# TCA6408A.net
KiCad netlist of a schematic drawn in EasyEDA Pro
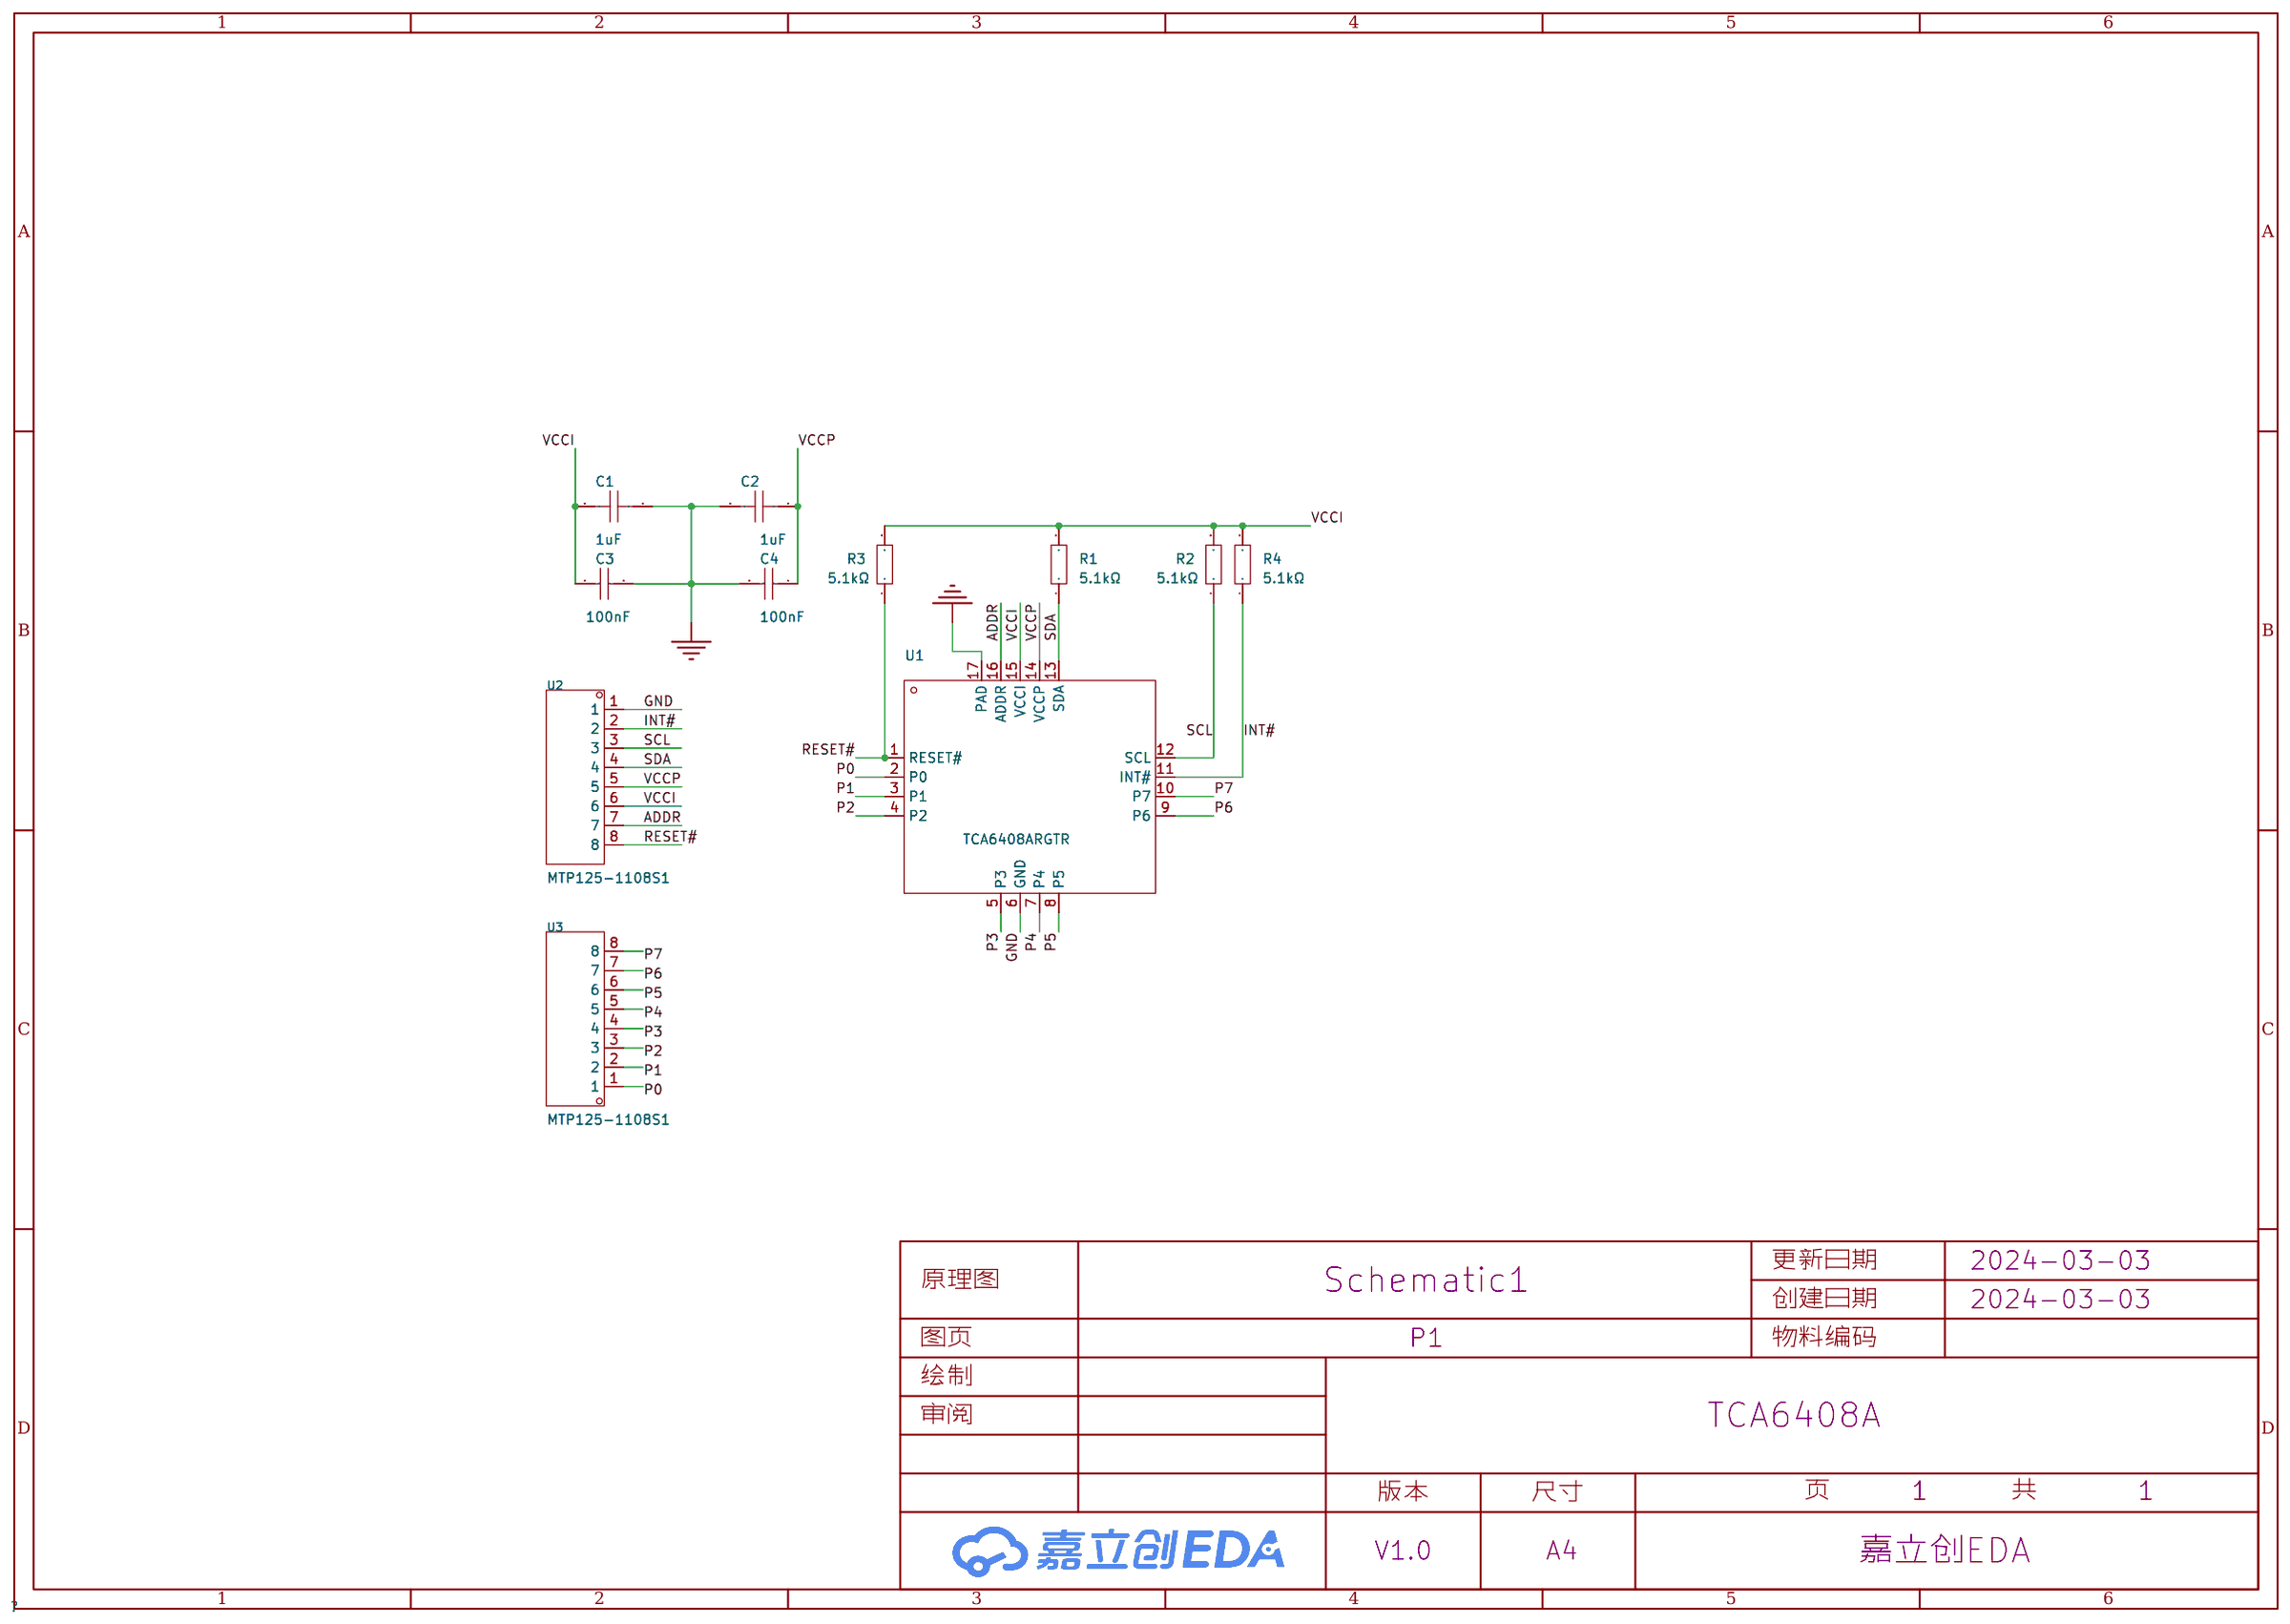
[diagram p0: schematic sheet]

(export (version "E")
  (design (tool "Eeschema 10.0.6"))
  (components
    (comp (ref "C1")
      (value "1uF")
      (footprint "easyedapro:C0402")
      (description "容值:1uF;精度:±10%;额定电压:25V;材质(温度系数):X5R;")
      (fields
        (field (name "Manufacturer Part") "CL05A105KA5NQNC")
        (field (name "Manufacturer") "SAMSUNG(三星)")
      )
      (libsource (lib "easyedapro") (part "CL05A105KA5NQNC"))
    )
    (comp (ref "C2")
      (value "1uF")
      (footprint "easyedapro:C0402")
      (description "容值:1uF;精度:±10%;额定电压:25V;材质(温度系数):X5R;")
      (fields
        (field (name "Manufacturer Part") "CL05A105KA5NQNC")
        (field (name "Manufacturer") "SAMSUNG(三星)")
      )
      (libsource (lib "easyedapro") (part "CL05A105KA5NQNC"))
    )
    (comp (ref "C3")
      (value "100nF")
      (footprint "easyedapro:C0402")
      (description "容值:100nF;精度:±10%;额定电压:16V;材质(温度系数):X7R;")
      (fields
        (field (name "Manufacturer Part") "CL05B104KO5NNNC")
        (field (name "Manufacturer") "SAMSUNG(三星)")
      )
      (libsource (lib "easyedapro") (part "CL05B104KO5NNNC"))
    )
    (comp (ref "C4")
      (value "100nF")
      (footprint "easyedapro:C0402")
      (description "容值:100nF;精度:±10%;额定电压:16V;材质(温度系数):X7R;")
      (fields
        (field (name "Manufacturer Part") "CL05B104KO5NNNC")
        (field (name "Manufacturer") "SAMSUNG(三星)")
      )
      (libsource (lib "easyedapro") (part "CL05B104KO5NNNC"))
    )
    (comp (ref "R1")
      (value "5.1kΩ")
      (footprint "easyedapro:R0402")
      (description "电阻类型:厚膜电阻;阻值:5.1kΩ;精度:±1%;功率:62.5mW;最大工作电压:50V;温度系数:±100ppm/°C;")
      (fields
        (field (name "Manufacturer Part") "0402WGF5101TCE")
        (field (name "Manufacturer") "UNI-ROYAL(厚声)")
      )
      (libsource (lib "easyedapro") (part "0402WGF5101TCE"))
    )
    (comp (ref "R2")
      (value "5.1kΩ")
      (footprint "easyedapro:R0402")
      (description "电阻类型:厚膜电阻;阻值:5.1kΩ;精度:±1%;功率:62.5mW;最大工作电压:50V;温度系数:±100ppm/°C;")
      (fields
        (field (name "Manufacturer Part") "0402WGF5101TCE")
        (field (name "Manufacturer") "UNI-ROYAL(厚声)")
      )
      (libsource (lib "easyedapro") (part "0402WGF5101TCE"))
    )
    (comp (ref "R3")
      (value "5.1kΩ")
      (footprint "easyedapro:R0402")
      (description "电阻类型:厚膜电阻;阻值:5.1kΩ;精度:±1%;功率:62.5mW;最大工作电压:50V;温度系数:±100ppm/°C;")
      (fields
        (field (name "Manufacturer Part") "0402WGF5101TCE")
        (field (name "Manufacturer") "UNI-ROYAL(厚声)")
      )
      (libsource (lib "easyedapro") (part "0402WGF5101TCE"))
    )
    (comp (ref "R4")
      (value "5.1kΩ")
      (footprint "easyedapro:R0402")
      (description "电阻类型:厚膜电阻;阻值:5.1kΩ;精度:±1%;功率:62.5mW;最大工作电压:50V;温度系数:±100ppm/°C;")
      (fields
        (field (name "Manufacturer Part") "0402WGF5101TCE")
        (field (name "Manufacturer") "UNI-ROYAL(厚声)")
      )
      (libsource (lib "easyedapro") (part "0402WGF5101TCE"))
    )
    (comp (ref "U1")
      (value "TCA6408ARGTR")
      (footprint "easyedapro:QFN-16_L3.0-W3.0-P0.50-BL-EP1.7")
      (description "接口:I2C；SMBus;I/O数量:8;时钟频率:400kHz;")
      (fields (field (name "Manufacturer") "TI(德州仪器)"))
      (libsource (lib "easyedapro") (part "TCA6408ARGTR"))
    )
    (comp (ref "U2")
      (value "MTP125-1108S1")
      (footprint "easyedapro:HDR-TH_8P-P2.54-H-M")
      (fields (field (name "Manufacturer") "MINTRON(明硕)"))
      (libsource (lib "easyedapro") (part "MTP125-1108S1"))
    )
    (comp (ref "U3")
      (value "MTP125-1108S1")
      (footprint "easyedapro:HDR-TH_8P-P2.54-H-M")
      (fields (field (name "Manufacturer") "MINTRON(明硕)"))
      (libsource (lib "easyedapro") (part "MTP125-1108S1"))
    )
  )
  (nets
    (net (code "1") (name "/ADDR") (class "Default")
      (node (ref "U1") (pin "16") (pinfunction "ADDR_16") (pintype "input"))
      (node (ref "U2") (pin "7") (pinfunction "7_7") (pintype "input"))
    )
    (net (code "2") (name "/INT#") (class "Default")
      (node (ref "R4") (pin "1") (pinfunction "1_1") (pintype "input"))
      (node (ref "U1") (pin "11") (pinfunction "INT#_11") (pintype "input"))
      (node (ref "U2") (pin "2") (pinfunction "2_2") (pintype "input"))
    )
    (net (code "3") (name "/P0") (class "Default")
      (node (ref "U1") (pin "2") (pinfunction "P0_2") (pintype "input"))
      (node (ref "U3") (pin "1") (pinfunction "1_1") (pintype "input"))
    )
    (net (code "4") (name "/P1") (class "Default")
      (node (ref "U1") (pin "3") (pinfunction "P1_3") (pintype "input"))
      (node (ref "U3") (pin "2") (pinfunction "2_2") (pintype "input"))
    )
    (net (code "5") (name "/P2") (class "Default")
      (node (ref "U1") (pin "4") (pinfunction "P2_4") (pintype "input"))
      (node (ref "U3") (pin "3") (pinfunction "3_3") (pintype "input"))
    )
    (net (code "6") (name "/P3") (class "Default")
      (node (ref "U1") (pin "5") (pinfunction "P3_5") (pintype "input"))
      (node (ref "U3") (pin "4") (pinfunction "4_4") (pintype "input"))
    )
    (net (code "7") (name "/P4") (class "Default")
      (node (ref "U1") (pin "7") (pinfunction "P4_7") (pintype "input"))
      (node (ref "U3") (pin "5") (pinfunction "5_5") (pintype "input"))
    )
    (net (code "8") (name "/P5") (class "Default")
      (node (ref "U1") (pin "8") (pinfunction "P5_8") (pintype "input"))
      (node (ref "U3") (pin "6") (pinfunction "6_6") (pintype "input"))
    )
    (net (code "9") (name "/P6") (class "Default")
      (node (ref "U1") (pin "9") (pinfunction "P6_9") (pintype "input"))
      (node (ref "U3") (pin "7") (pinfunction "7_7") (pintype "input"))
    )
    (net (code "10") (name "/P7") (class "Default")
      (node (ref "U1") (pin "10") (pinfunction "P7_10") (pintype "input"))
      (node (ref "U3") (pin "8") (pinfunction "8_8") (pintype "input"))
    )
    (net (code "11") (name "/RESET#") (class "Default")
      (node (ref "R3") (pin "1") (pinfunction "1_1") (pintype "input"))
      (node (ref "U1") (pin "1") (pinfunction "RESET#_1") (pintype "input"))
      (node (ref "U2") (pin "8") (pinfunction "8_8") (pintype "input"))
    )
    (net (code "12") (name "/SCL") (class "Default")
      (node (ref "R2") (pin "1") (pinfunction "1_1") (pintype "input"))
      (node (ref "U1") (pin "12") (pinfunction "SCL_12") (pintype "input"))
      (node (ref "U2") (pin "3") (pinfunction "3_3") (pintype "input"))
    )
    (net (code "13") (name "/SDA") (class "Default")
      (node (ref "R1") (pin "1") (pinfunction "1_1") (pintype "input"))
      (node (ref "U1") (pin "13") (pinfunction "SDA_13") (pintype "input"))
      (node (ref "U2") (pin "4") (pinfunction "4_4") (pintype "input"))
    )
    (net (code "14") (name "/VCCI") (class "Default")
      (node (ref "C1") (pin "2") (pinfunction "2_2") (pintype "unspecified"))
      (node (ref "C3") (pin "2") (pinfunction "2_2") (pintype "input"))
      (node (ref "R1") (pin "2") (pinfunction "2_2") (pintype "input"))
      (node (ref "R2") (pin "2") (pinfunction "2_2") (pintype "input"))
      (node (ref "R3") (pin "2") (pinfunction "2_2") (pintype "input"))
      (node (ref "R4") (pin "2") (pinfunction "2_2") (pintype "input"))
      (node (ref "U1") (pin "15") (pinfunction "VCCI_15") (pintype "input"))
      (node (ref "U2") (pin "6") (pinfunction "6_6") (pintype "input"))
    )
    (net (code "15") (name "/VCCP") (class "Default")
      (node (ref "C2") (pin "1") (pinfunction "1_1") (pintype "unspecified"))
      (node (ref "C4") (pin "1") (pinfunction "1_1") (pintype "input"))
      (node (ref "U1") (pin "14") (pinfunction "VCCP_14") (pintype "input"))
      (node (ref "U2") (pin "5") (pinfunction "5_5") (pintype "input"))
    )
    (net (code "16") (name "GND") (class "Default")
      (node (ref "C1") (pin "1") (pinfunction "1_1") (pintype "unspecified"))
      (node (ref "C2") (pin "2") (pinfunction "2_2") (pintype "unspecified"))
      (node (ref "C3") (pin "1") (pinfunction "1_1") (pintype "input"))
      (node (ref "C4") (pin "2") (pinfunction "2_2") (pintype "input"))
      (node (ref "U1") (pin "17") (pinfunction "PAD_17") (pintype "input"))
      (node (ref "U1") (pin "6") (pinfunction "GND_6") (pintype "input"))
      (node (ref "U2") (pin "1") (pinfunction "1_1") (pintype "input"))
    )
  )
)
